# REL1_eagle7x.net
KiCad netlist of a schematic drawn in EAGLE
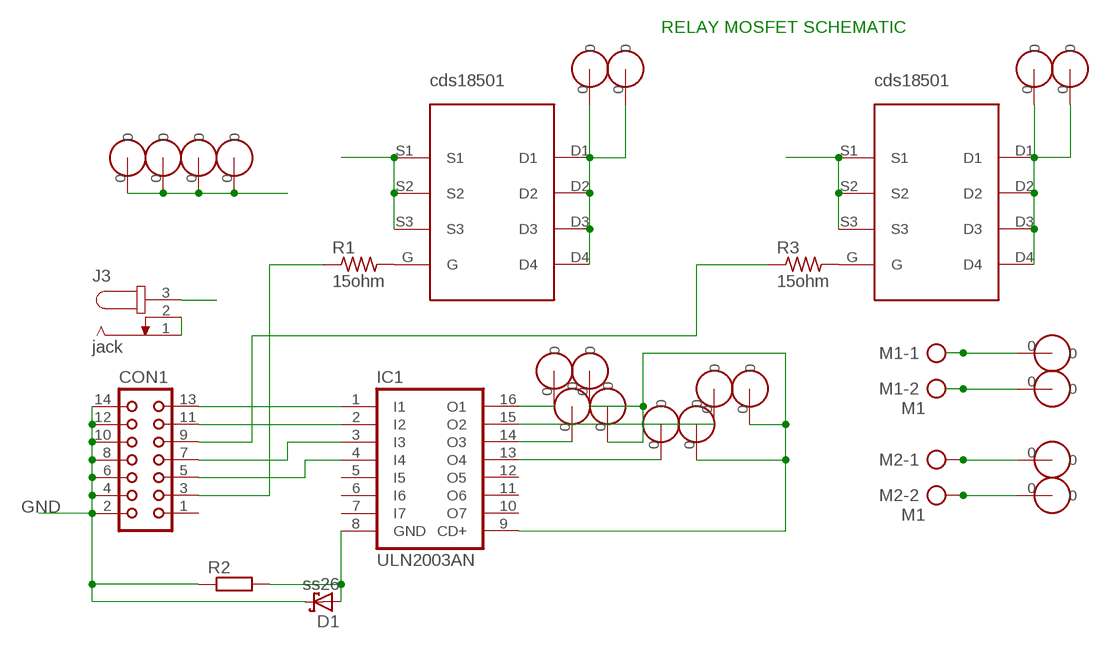
[diagram p0: schematic, sheet 1]

(export (version "E")
  (design (tool "Eeschema 10.0.6"))
  (components
    (comp (ref "24V")
      (value "PAD0")
      (footprint "eagle-import:SWITCHPAD")
      (libsource (lib "eagle-import") (part "PAD0"))
    )
    (comp (ref "CON1")
      (value "CON14")
      (footprint "eagle-import:CON14")
      (libsource (lib "eagle-import") (part "CON14"))
    )
    (comp (ref "D1")
      (value "ss26")
      (footprint "eagle-import:SMB")
      (libsource (lib "eagle-import") (part "SCHOTTKY-DIODESMD"))
    )
    (comp (ref "IC1")
      (value "ULN2003AN")
      (footprint "eagle-import:DIL16")
      (libsource (lib "eagle-import") (part "ULN2003AN"))
    )
    (comp (ref "J3")
      (value "jack")
      (footprint "eagle-import:SPC4077")
      (libsource (lib "eagle-import") (part "JACK-PLUG0"))
    )
    (comp (ref "M1")
      (value "M1")
      (footprint "eagle-import:AK300_2")
      (libsource (lib "eagle-import") (part "AK300/2"))
    )
    (comp (ref "M2")
      (value "M1")
      (footprint "eagle-import:AK300_2")
      (libsource (lib "eagle-import") (part "AK300/2"))
    )
    (comp (ref "R1")
      (value "15ohm")
      (footprint "eagle-import:M1206")
      (libsource (lib "eagle-import") (part "R-US_M1206"))
    )
    (comp (ref "R2")
      (value "R-EU_0414/15")
      (footprint "eagle-import:0414_15")
      (libsource (lib "eagle-import") (part "R-EU_0414/15"))
    )
    (comp (ref "R3")
      (value "15ohm")
      (footprint "eagle-import:M1206")
      (libsource (lib "eagle-import") (part "R-US_M1206"))
    )
    (comp (ref "U$1")
      (value "PAD0")
      (footprint "eagle-import:SWITCHPAD")
      (libsource (lib "eagle-import") (part "PAD0"))
    )
    (comp (ref "U$2")
      (value "PAD0")
      (footprint "eagle-import:SWITCHPAD")
      (libsource (lib "eagle-import") (part "PAD0"))
    )
    (comp (ref "U$3")
      (value "PAD0")
      (footprint "eagle-import:SWITCHPAD")
      (libsource (lib "eagle-import") (part "PAD0"))
    )
    (comp (ref "U$4")
      (value "PAD0")
      (footprint "eagle-import:SWITCHPAD")
      (libsource (lib "eagle-import") (part "PAD0"))
    )
    (comp (ref "U$5")
      (value "PAD0")
      (footprint "eagle-import:SWITCHPAD")
      (libsource (lib "eagle-import") (part "PAD0"))
    )
    (comp (ref "U$6")
      (value "PAD0")
      (footprint "eagle-import:SWITCHPAD")
      (libsource (lib "eagle-import") (part "PAD0"))
    )
    (comp (ref "U$7")
      (value "PAD0")
      (footprint "eagle-import:SWITCHPAD")
      (libsource (lib "eagle-import") (part "PAD0"))
    )
    (comp (ref "U$8")
      (value "PAD0")
      (footprint "eagle-import:SWITCHPAD")
      (libsource (lib "eagle-import") (part "PAD0"))
    )
    (comp (ref "U$9")
      (value "PAD0")
      (footprint "eagle-import:SWITCHPAD")
      (libsource (lib "eagle-import") (part "PAD0"))
    )
    (comp (ref "U$10")
      (value "PAD0")
      (footprint "eagle-import:SWITCHPAD")
      (libsource (lib "eagle-import") (part "PAD0"))
    )
    (comp (ref "U$11")
      (value "CSD18503GDS-NEW")
      (footprint "eagle-import:CDS")
      (libsource (lib "eagle-import") (part "CSD18503GDS-NEW"))
    )
    (comp (ref "U$12")
      (value "CSD18503GDS-NEW")
      (footprint "eagle-import:CDS")
      (libsource (lib "eagle-import") (part "CSD18503GDS-NEW"))
    )
    (comp (ref "U$13")
      (value "PAD0")
      (footprint "eagle-import:SWITCHPAD")
      (libsource (lib "eagle-import") (part "PAD0"))
    )
    (comp (ref "U$14")
      (value "PAD0")
      (footprint "eagle-import:SWITCHPAD")
      (libsource (lib "eagle-import") (part "PAD0"))
    )
    (comp (ref "U$15")
      (value "PAD0")
      (footprint "eagle-import:SWITCHPAD")
      (libsource (lib "eagle-import") (part "PAD0"))
    )
    (comp (ref "U$16")
      (value "PAD0")
      (footprint "eagle-import:SWITCHPAD")
      (libsource (lib "eagle-import") (part "PAD0"))
    )
    (comp (ref "U$17")
      (value "PAD0")
      (footprint "eagle-import:SWITCHPAD")
      (libsource (lib "eagle-import") (part "PAD0"))
    )
    (comp (ref "U$18")
      (value "PAD0")
      (footprint "eagle-import:SWITCHPAD")
      (libsource (lib "eagle-import") (part "PAD0"))
    )
    (comp (ref "U$19")
      (value "PAD0")
      (footprint "eagle-import:SWITCHPAD")
      (libsource (lib "eagle-import") (part "PAD0"))
    )
    (comp (ref "U$20")
      (value "PAD0")
      (footprint "eagle-import:SWITCHPAD")
      (libsource (lib "eagle-import") (part "PAD0"))
    )
    (comp (ref "U$21")
      (value "PAD0")
      (footprint "eagle-import:SWITCHPAD")
      (libsource (lib "eagle-import") (part "PAD0"))
    )
  )
  (nets
    (net (code "1") (name "/24V") (class "Default")
      (node (ref "24V") (pin "0") (pinfunction "0_0") (pintype "bidirectional"))
      (node (ref "IC1") (pin "9") (pinfunction "CD+_9") (pintype "passive"))
      (node (ref "J3") (pin "3") (pinfunction "3_3") (pintype "passive"))
      (node (ref "U$10") (pin "0") (pinfunction "0_0") (pintype "bidirectional"))
      (node (ref "U$21") (pin "0") (pinfunction "0_0") (pintype "bidirectional"))
      (node (ref "U$3") (pin "0") (pinfunction "0_0") (pintype "bidirectional"))
      (node (ref "U$4") (pin "0") (pinfunction "0_0") (pintype "bidirectional"))
      (node (ref "U$6") (pin "0") (pinfunction "0_0") (pintype "bidirectional"))
      (node (ref "U$8") (pin "0") (pinfunction "0_0") (pintype "bidirectional"))
      (node (ref "U$9") (pin "0") (pinfunction "0_0") (pintype "bidirectional"))
    )
    (net (code "2") (name "/GND") (class "Default")
      (node (ref "CON1") (pin "10") (pinfunction "10_10") (pintype "passive"))
      (node (ref "CON1") (pin "12") (pinfunction "12_12") (pintype "passive"))
      (node (ref "CON1") (pin "14") (pinfunction "14_14") (pintype "passive"))
      (node (ref "CON1") (pin "2") (pinfunction "2_2") (pintype "passive"))
      (node (ref "CON1") (pin "4") (pinfunction "4_4") (pintype "passive"))
      (node (ref "CON1") (pin "6") (pinfunction "6_6") (pintype "passive"))
      (node (ref "CON1") (pin "8") (pinfunction "8_8") (pintype "passive"))
      (node (ref "D1") (pin "C") (pinfunction "C_C") (pintype "passive"))
      (node (ref "J3") (pin "1") (pinfunction "1_1") (pintype "passive"))
      (node (ref "J3") (pin "2") (pinfunction "2_2") (pintype "passive"))
      (node (ref "R2") (pin "1") (pinfunction "1_1") (pintype "passive"))
      (node (ref "U$11") (pin "S1") (pinfunction "S1_S1") (pintype "bidirectional"))
      (node (ref "U$11") (pin "S2") (pinfunction "S2_S2") (pintype "bidirectional"))
      (node (ref "U$11") (pin "S3") (pinfunction "S3_S3") (pintype "bidirectional"))
      (node (ref "U$12") (pin "S1") (pinfunction "S1_S1") (pintype "bidirectional"))
      (node (ref "U$12") (pin "S2") (pinfunction "S2_S2") (pintype "bidirectional"))
      (node (ref "U$12") (pin "S3") (pinfunction "S3_S3") (pintype "bidirectional"))
    )
    (net (code "3") (name "Net-(CON1-Pad3)") (class "Default")
      (node (ref "CON1") (pin "3") (pinfunction "3_3") (pintype "passive"))
      (node (ref "R1") (pin "1") (pinfunction "1_1") (pintype "passive"))
    )
    (net (code "4") (name "Net-(CON1-Pad9)") (class "Default")
      (node (ref "CON1") (pin "9") (pinfunction "9_9") (pintype "passive"))
      (node (ref "R3") (pin "1") (pinfunction "1_1") (pintype "passive"))
    )
    (net (code "5") (name "Net-(IC1-GND)") (class "Default")
      (node (ref "D1") (pin "A") (pinfunction "A_A") (pintype "passive"))
      (node (ref "IC1") (pin "8") (pinfunction "GND_8") (pintype "power_in"))
      (node (ref "R2") (pin "2") (pinfunction "2_2") (pintype "passive"))
    )
    (net (code "6") (name "Net-(IC1-I1)") (class "Default")
      (node (ref "CON1") (pin "13") (pinfunction "13_13") (pintype "passive"))
      (node (ref "IC1") (pin "1") (pinfunction "I1_1") (pintype "input"))
    )
    (net (code "7") (name "Net-(IC1-I2)") (class "Default")
      (node (ref "CON1") (pin "11") (pinfunction "11_11") (pintype "passive"))
      (node (ref "IC1") (pin "2") (pinfunction "I2_2") (pintype "input"))
    )
    (net (code "8") (name "Net-(IC1-I3)") (class "Default")
      (node (ref "CON1") (pin "7") (pinfunction "7_7") (pintype "passive"))
      (node (ref "IC1") (pin "3") (pinfunction "I3_3") (pintype "input"))
    )
    (net (code "9") (name "Net-(IC1-I4)") (class "Default")
      (node (ref "CON1") (pin "5") (pinfunction "5_5") (pintype "passive"))
      (node (ref "IC1") (pin "4") (pinfunction "I4_4") (pintype "input"))
    )
    (net (code "10") (name "Net-(IC1-O1)") (class "Default")
      (node (ref "IC1") (pin "16") (pinfunction "O1_16") (pintype "open_collector"))
      (node (ref "U$1") (pin "0") (pinfunction "0_0") (pintype "bidirectional"))
    )
    (net (code "11") (name "Net-(IC1-O2)") (class "Default")
      (node (ref "IC1") (pin "15") (pinfunction "O2_15") (pintype "open_collector"))
      (node (ref "U$2") (pin "0") (pinfunction "0_0") (pintype "bidirectional"))
    )
    (net (code "12") (name "Net-(IC1-O3)") (class "Default")
      (node (ref "IC1") (pin "14") (pinfunction "O3_14") (pintype "open_collector"))
      (node (ref "U$5") (pin "0") (pinfunction "0_0") (pintype "bidirectional"))
    )
    (net (code "13") (name "Net-(IC1-O4)") (class "Default")
      (node (ref "IC1") (pin "13") (pinfunction "O4_13") (pintype "open_collector"))
      (node (ref "U$7") (pin "0") (pinfunction "0_0") (pintype "bidirectional"))
    )
    (net (code "14") (name "Net-(M1A-KL)") (class "Default")
      (node (ref "M1") (pin "1") (pinfunction "KL_1") (pintype "passive"))
      (node (ref "U$17") (pin "0") (pinfunction "0_0") (pintype "bidirectional"))
    )
    (net (code "15") (name "Net-(M1B-KL)") (class "Default")
      (node (ref "M1") (pin "2") (pinfunction "KL_2") (pintype "passive"))
      (node (ref "U$18") (pin "0") (pinfunction "0_0") (pintype "bidirectional"))
    )
    (net (code "16") (name "Net-(M2A-KL)") (class "Default")
      (node (ref "M2") (pin "1") (pinfunction "KL_1") (pintype "passive"))
      (node (ref "U$19") (pin "0") (pinfunction "0_0") (pintype "bidirectional"))
    )
    (net (code "17") (name "Net-(M2B-KL)") (class "Default")
      (node (ref "M2") (pin "2") (pinfunction "KL_2") (pintype "passive"))
      (node (ref "U$20") (pin "0") (pinfunction "0_0") (pintype "bidirectional"))
    )
    (net (code "18") (name "Net-(R1-Pad2)") (class "Default")
      (node (ref "R1") (pin "2") (pinfunction "2_2") (pintype "passive"))
      (node (ref "U$11") (pin "G") (pinfunction "G_G") (pintype "bidirectional"))
    )
    (net (code "19") (name "Net-(R3-Pad2)") (class "Default")
      (node (ref "R3") (pin "2") (pinfunction "2_2") (pintype "passive"))
      (node (ref "U$12") (pin "G") (pinfunction "G_G") (pintype "bidirectional"))
    )
    (net (code "20") (name "Net-(U$11-PadD1)") (class "Default")
      (node (ref "U$11") (pin "D1") (pinfunction "D1_D1") (pintype "bidirectional"))
      (node (ref "U$11") (pin "D2") (pinfunction "D2_D2") (pintype "bidirectional"))
      (node (ref "U$11") (pin "D3") (pinfunction "D3_D3") (pintype "bidirectional"))
      (node (ref "U$11") (pin "D4") (pinfunction "D4_D4") (pintype "bidirectional"))
      (node (ref "U$13") (pin "0") (pinfunction "0_0") (pintype "bidirectional"))
      (node (ref "U$15") (pin "0") (pinfunction "0_0") (pintype "bidirectional"))
    )
    (net (code "21") (name "Net-(U$12-PadD1)") (class "Default")
      (node (ref "U$12") (pin "D1") (pinfunction "D1_D1") (pintype "bidirectional"))
      (node (ref "U$12") (pin "D2") (pinfunction "D2_D2") (pintype "bidirectional"))
      (node (ref "U$12") (pin "D3") (pinfunction "D3_D3") (pintype "bidirectional"))
      (node (ref "U$12") (pin "D4") (pinfunction "D4_D4") (pintype "bidirectional"))
      (node (ref "U$14") (pin "0") (pinfunction "0_0") (pintype "bidirectional"))
      (node (ref "U$16") (pin "0") (pinfunction "0_0") (pintype "bidirectional"))
    )
    (net (code "22") (name "unconnected-(CON1-Pad1)") (class "Default")
      (node (ref "CON1") (pin "1") (pinfunction "1_1") (pintype "passive"))
    )
    (net (code "23") (name "unconnected-(IC1-I5-Pad5)") (class "Default")
      (node (ref "IC1") (pin "5") (pinfunction "I5_5") (pintype "input"))
    )
    (net (code "24") (name "unconnected-(IC1-I6-Pad6)") (class "Default")
      (node (ref "IC1") (pin "6") (pinfunction "I6_6") (pintype "input"))
    )
    (net (code "25") (name "unconnected-(IC1-I7-Pad7)") (class "Default")
      (node (ref "IC1") (pin "7") (pinfunction "I7_7") (pintype "input"))
    )
    (net (code "26") (name "unconnected-(IC1-O5-Pad12)") (class "Default")
      (node (ref "IC1") (pin "12") (pinfunction "O5_12") (pintype "open_collector"))
    )
    (net (code "27") (name "unconnected-(IC1-O6-Pad11)") (class "Default")
      (node (ref "IC1") (pin "11") (pinfunction "O6_11") (pintype "open_collector"))
    )
    (net (code "28") (name "unconnected-(IC1-O7-Pad10)") (class "Default")
      (node (ref "IC1") (pin "10") (pinfunction "O7_10") (pintype "open_collector"))
    )
  )
)
